# throughhole.net
KiCad netlist of a schematic drawn in EAGLE
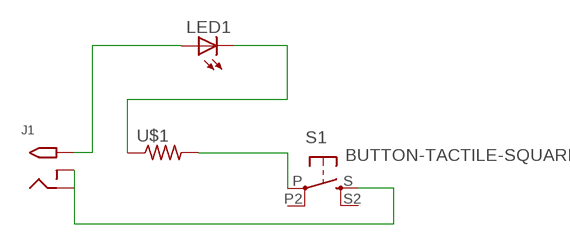
[diagram p0: schematic, sheet 1]

(export (version "E")
  (design (tool "Eeschema 10.0.6"))
  (components
    (comp (ref "J1")
      (value "2.1MMJACKTHM")
      (footprint "eagle-import:PJ-102A")
      (libsource (lib "eagle-import") (part "2.1MMJACKTHM"))
    )
    (comp (ref "LED1")
      (value "LED5MM")
      (footprint "eagle-import:LED5MM")
      (libsource (lib "eagle-import") (part "LED5MM"))
    )
    (comp (ref "S1")
      (value "BUTTON-TACTILE-SQUARE")
      (footprint "eagle-import:BUTTON-TACTILE-SQUARE-ADAFRUIT1010")
      (libsource (lib "eagle-import") (part "BUTTON-TACTILE-SQUARE"))
    )
    (comp (ref "U$1")
      (value "RESISTORTH-1/4W-CARBON")
      (footprint "eagle-import:RESAD1160W55L680D260_HS")
      (libsource (lib "eagle-import") (part "RESISTORTH-1/4W-CARBON"))
    )
  )
  (nets
    (net (code "1") (name "Net-(J1-PadRING)") (class "Default")
      (node (ref "J1") (pin "RING") (pinfunction "RING_RING") (pintype "bidirectional"))
      (node (ref "J1") (pin "RING_SW") (pinfunction "RING_SW_RING_SW") (pintype "bidirectional"))
      (node (ref "S1") (pin "S") (pinfunction "S_S") (pintype "passive"))
    )
    (net (code "2") (name "Net-(J1-PadTIP)") (class "Default")
      (node (ref "J1") (pin "TIP") (pinfunction "TIP_TIP") (pintype "bidirectional"))
      (node (ref "LED1") (pin "A") (pinfunction "A_A") (pintype "passive"))
    )
    (net (code "3") (name "Net-(LED1-C)") (class "Default")
      (node (ref "LED1") (pin "K") (pinfunction "C_K") (pintype "passive"))
      (node (ref "U$1") (pin "1") (pinfunction "1_1") (pintype "passive"))
    )
    (net (code "4") (name "Net-(S1-PadP)") (class "Default")
      (node (ref "S1") (pin "P") (pinfunction "P_P") (pintype "passive"))
      (node (ref "U$1") (pin "2") (pinfunction "2_2") (pintype "passive"))
    )
    (net (code "5") (name "unconnected-(S1-P1-PadP2)") (class "Default")
      (node (ref "S1") (pin "P2") (pinfunction "P1_P2") (pintype "passive"))
    )
    (net (code "6") (name "unconnected-(S1-S1-PadS2)") (class "Default")
      (node (ref "S1") (pin "S2") (pinfunction "S1_S2") (pintype "passive"))
    )
  )
)
